# Precision_Adder.net
KiCad netlist of a schematic drawn in EAGLE
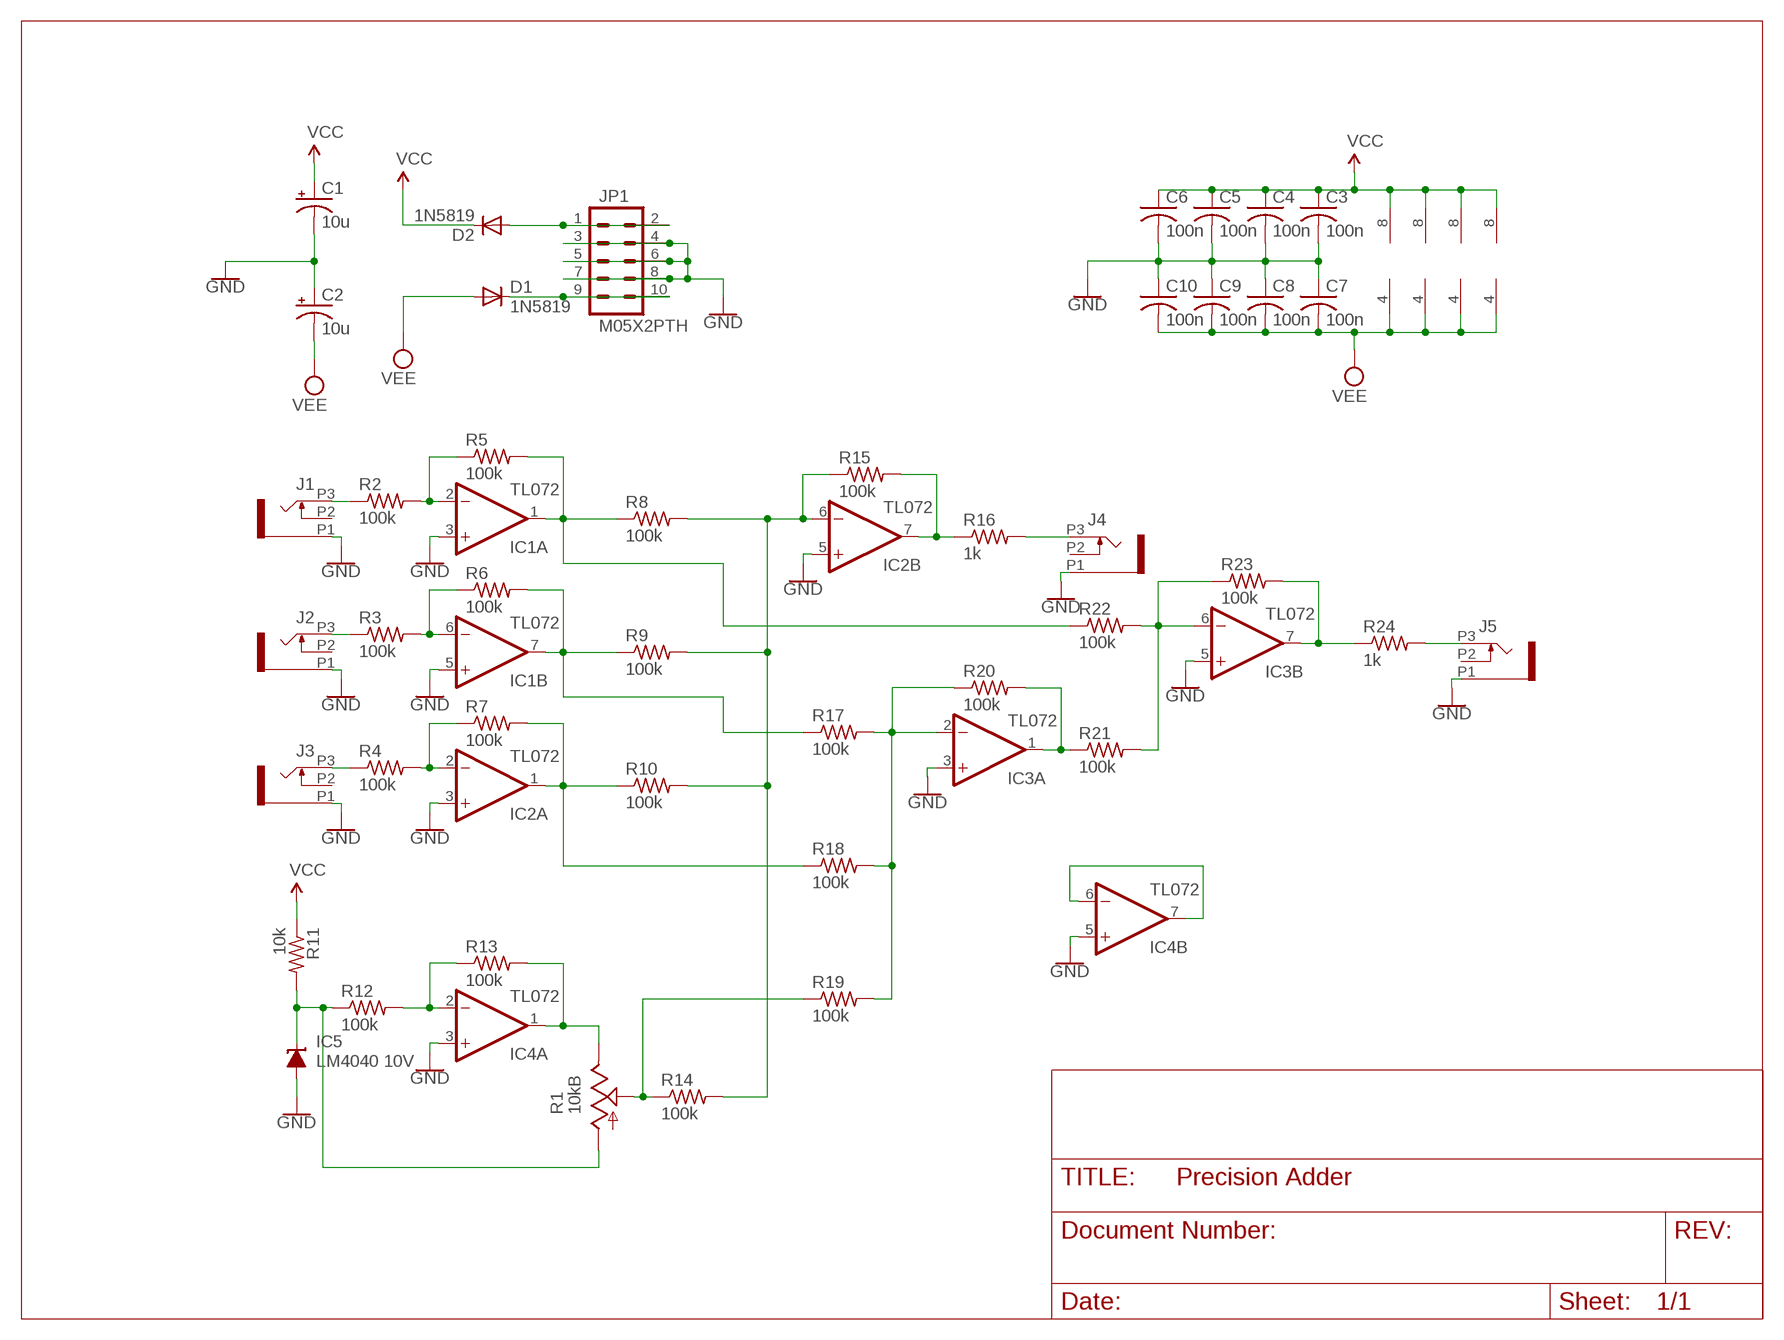
[diagram p0: schematic, sheet 1]

(export (version "E")
  (design (tool "Eeschema 10.0.6"))
  (components
    (comp (ref "C1")
      (value "10u")
      (footprint "eagle-import:RCL_PANASONIC_B")
      (libsource (lib "eagle-import") (part "RCL_CPOL-USB"))
    )
    (comp (ref "C2")
      (value "10u")
      (footprint "eagle-import:RCL_PANASONIC_B")
      (libsource (lib "eagle-import") (part "RCL_CPOL-USB"))
    )
    (comp (ref "C3")
      (value "100n")
      (footprint "eagle-import:RCL_C0603")
      (libsource (lib "eagle-import") (part "RCL_C-USC0603"))
    )
    (comp (ref "C4")
      (value "100n")
      (footprint "eagle-import:RCL_C0603")
      (libsource (lib "eagle-import") (part "RCL_C-USC0603"))
    )
    (comp (ref "C5")
      (value "100n")
      (footprint "eagle-import:RCL_C0603")
      (libsource (lib "eagle-import") (part "RCL_C-USC0603"))
    )
    (comp (ref "C6")
      (value "100n")
      (footprint "eagle-import:RCL_C0603")
      (libsource (lib "eagle-import") (part "RCL_C-USC0603"))
    )
    (comp (ref "C7")
      (value "100n")
      (footprint "eagle-import:RCL_C0603")
      (libsource (lib "eagle-import") (part "RCL_C-USC0603"))
    )
    (comp (ref "C8")
      (value "100n")
      (footprint "eagle-import:RCL_C0603")
      (libsource (lib "eagle-import") (part "RCL_C-USC0603"))
    )
    (comp (ref "C9")
      (value "100n")
      (footprint "eagle-import:RCL_C0603")
      (libsource (lib "eagle-import") (part "RCL_C-USC0603"))
    )
    (comp (ref "C10")
      (value "100n")
      (footprint "eagle-import:RCL_C0603")
      (libsource (lib "eagle-import") (part "RCL_C-USC0603"))
    )
    (comp (ref "D1")
      (value "1N5819")
      (footprint "eagle-import:DIODE_SOD123")
      (libsource (lib "eagle-import") (part "DIODE_DIODE-SOD123"))
    )
    (comp (ref "D2")
      (value "1N5819")
      (footprint "eagle-import:DIODE_SOD123")
      (libsource (lib "eagle-import") (part "DIODE_DIODE-SOD123"))
    )
    (comp (ref "IC1")
      (value "TL072")
      (footprint "eagle-import:GM-ICS_SO08")
      (libsource (lib "eagle-import") (part "GM-ICS_TL072D"))
    )
    (comp (ref "IC2")
      (value "TL072")
      (footprint "eagle-import:GM-ICS_SO08")
      (libsource (lib "eagle-import") (part "GM-ICS_TL072D"))
    )
    (comp (ref "IC3")
      (value "TL072")
      (footprint "eagle-import:GM-ICS_SO08")
      (libsource (lib "eagle-import") (part "GM-ICS_TL072D"))
    )
    (comp (ref "IC4")
      (value "TL072")
      (footprint "eagle-import:GM-ICS_SO08")
      (libsource (lib "eagle-import") (part "GM-ICS_TL072D"))
    )
    (comp (ref "IC5")
      (value "LM4040 10V")
      (footprint "eagle-import:TEXAS_DBZ_R-PDSO-G3")
      (libsource (lib "eagle-import") (part "TEXAS_LM4041DBZA12"))
    )
    (comp (ref "J1")
      (value "OG-PJ301_PJ301_THONKICONN6")
      (footprint "eagle-import:OG-PJ301_WQP_PJ_301M6")
      (libsource (lib "eagle-import") (part "OG-PJ301_PJ301_THONKICONN6"))
    )
    (comp (ref "J2")
      (value "OG-PJ301_PJ301_THONKICONN6")
      (footprint "eagle-import:OG-PJ301_WQP_PJ_301M6")
      (libsource (lib "eagle-import") (part "OG-PJ301_PJ301_THONKICONN6"))
    )
    (comp (ref "J3")
      (value "OG-PJ301_PJ301_THONKICONN6")
      (footprint "eagle-import:OG-PJ301_WQP_PJ_301M6")
      (libsource (lib "eagle-import") (part "OG-PJ301_PJ301_THONKICONN6"))
    )
    (comp (ref "J4")
      (value "OG-PJ301_PJ301_THONKICONN6")
      (footprint "eagle-import:OG-PJ301_WQP_PJ_301M6")
      (libsource (lib "eagle-import") (part "OG-PJ301_PJ301_THONKICONN6"))
    )
    (comp (ref "J5")
      (value "OG-PJ301_PJ301_THONKICONN6")
      (footprint "eagle-import:OG-PJ301_WQP_PJ_301M6")
      (libsource (lib "eagle-import") (part "OG-PJ301_PJ301_THONKICONN6"))
    )
    (comp (ref "JP1")
      (value "M05X2PTH")
      (footprint "eagle-import:OG-HEADER_AVR_ICSP")
      (libsource (lib "eagle-import") (part "OG-HEADER_M05X2PTH"))
    )
    (comp (ref "R1")
      (value "10kB")
      (footprint "eagle-import:POT-ALPS_ALPS_POT_VERTICAL_PS")
      (libsource (lib "eagle-import") (part "POT-ALPS_POT_USVERTICAL_PS"))
    )
    (comp (ref "R2")
      (value "100k")
      (footprint "eagle-import:RESISTOR_R0603")
      (libsource (lib "eagle-import") (part "RESISTOR_R-US_R0603"))
    )
    (comp (ref "R3")
      (value "100k")
      (footprint "eagle-import:RESISTOR_R0603")
      (libsource (lib "eagle-import") (part "RESISTOR_R-US_R0603"))
    )
    (comp (ref "R4")
      (value "100k")
      (footprint "eagle-import:RESISTOR_R0603")
      (libsource (lib "eagle-import") (part "RESISTOR_R-US_R0603"))
    )
    (comp (ref "R5")
      (value "100k")
      (footprint "eagle-import:RESISTOR_R0603")
      (libsource (lib "eagle-import") (part "RESISTOR_R-US_R0603"))
    )
    (comp (ref "R6")
      (value "100k")
      (footprint "eagle-import:RESISTOR_R0603")
      (libsource (lib "eagle-import") (part "RESISTOR_R-US_R0603"))
    )
    (comp (ref "R7")
      (value "100k")
      (footprint "eagle-import:RESISTOR_R0603")
      (libsource (lib "eagle-import") (part "RESISTOR_R-US_R0603"))
    )
    (comp (ref "R8")
      (value "100k")
      (footprint "eagle-import:RESISTOR_R0603")
      (libsource (lib "eagle-import") (part "RESISTOR_R-US_R0603"))
    )
    (comp (ref "R9")
      (value "100k")
      (footprint "eagle-import:RESISTOR_R0603")
      (libsource (lib "eagle-import") (part "RESISTOR_R-US_R0603"))
    )
    (comp (ref "R10")
      (value "100k")
      (footprint "eagle-import:RESISTOR_R0603")
      (libsource (lib "eagle-import") (part "RESISTOR_R-US_R0603"))
    )
    (comp (ref "R11")
      (value "10k")
      (footprint "eagle-import:RESISTOR_R0603")
      (libsource (lib "eagle-import") (part "RESISTOR_R-US_R0603"))
    )
    (comp (ref "R12")
      (value "100k")
      (footprint "eagle-import:RESISTOR_R0603")
      (libsource (lib "eagle-import") (part "RESISTOR_R-US_R0603"))
    )
    (comp (ref "R13")
      (value "100k")
      (footprint "eagle-import:RESISTOR_R0603")
      (libsource (lib "eagle-import") (part "RESISTOR_R-US_R0603"))
    )
    (comp (ref "R14")
      (value "100k")
      (footprint "eagle-import:RESISTOR_R0603")
      (libsource (lib "eagle-import") (part "RESISTOR_R-US_R0603"))
    )
    (comp (ref "R15")
      (value "100k")
      (footprint "eagle-import:RESISTOR_R0603")
      (libsource (lib "eagle-import") (part "RESISTOR_R-US_R0603"))
    )
    (comp (ref "R16")
      (value "1k")
      (footprint "eagle-import:RESISTOR_R0603")
      (libsource (lib "eagle-import") (part "RESISTOR_R-US_R0603"))
    )
    (comp (ref "R17")
      (value "100k")
      (footprint "eagle-import:RESISTOR_R0603")
      (libsource (lib "eagle-import") (part "RESISTOR_R-US_R0603"))
    )
    (comp (ref "R18")
      (value "100k")
      (footprint "eagle-import:RESISTOR_R0603")
      (libsource (lib "eagle-import") (part "RESISTOR_R-US_R0603"))
    )
    (comp (ref "R19")
      (value "100k")
      (footprint "eagle-import:RESISTOR_R0603")
      (libsource (lib "eagle-import") (part "RESISTOR_R-US_R0603"))
    )
    (comp (ref "R20")
      (value "100k")
      (footprint "eagle-import:RESISTOR_R0603")
      (libsource (lib "eagle-import") (part "RESISTOR_R-US_R0603"))
    )
    (comp (ref "R21")
      (value "100k")
      (footprint "eagle-import:RESISTOR_R0603")
      (libsource (lib "eagle-import") (part "RESISTOR_R-US_R0603"))
    )
    (comp (ref "R22")
      (value "100k")
      (footprint "eagle-import:RESISTOR_R0603")
      (libsource (lib "eagle-import") (part "RESISTOR_R-US_R0603"))
    )
    (comp (ref "R23")
      (value "100k")
      (footprint "eagle-import:RESISTOR_R0603")
      (libsource (lib "eagle-import") (part "RESISTOR_R-US_R0603"))
    )
    (comp (ref "R24")
      (value "1k")
      (footprint "eagle-import:RESISTOR_R0603")
      (libsource (lib "eagle-import") (part "RESISTOR_R-US_R0603"))
    )
  )
  (nets
    (net (code "1") (name "GND") (class "Default")
      (node (ref "C1") (pin "-") (pinfunction "-_-") (pintype "passive"))
      (node (ref "C10") (pin "1") (pinfunction "1_1") (pintype "passive"))
      (node (ref "C2") (pin "+") (pinfunction "+_+") (pintype "passive"))
      (node (ref "C3") (pin "2") (pinfunction "2_2") (pintype "passive"))
      (node (ref "C4") (pin "2") (pinfunction "2_2") (pintype "passive"))
      (node (ref "C5") (pin "2") (pinfunction "2_2") (pintype "passive"))
      (node (ref "C6") (pin "2") (pinfunction "2_2") (pintype "passive"))
      (node (ref "C7") (pin "1") (pinfunction "1_1") (pintype "passive"))
      (node (ref "C8") (pin "1") (pinfunction "1_1") (pintype "passive"))
      (node (ref "C9") (pin "1") (pinfunction "1_1") (pintype "passive"))
      (node (ref "IC1") (pin "3") (pinfunction "+IN_3") (pintype "input"))
      (node (ref "IC1") (pin "5") (pinfunction "+IN_5") (pintype "input"))
      (node (ref "IC2") (pin "3") (pinfunction "+IN_3") (pintype "input"))
      (node (ref "IC2") (pin "5") (pinfunction "+IN_5") (pintype "input"))
      (node (ref "IC3") (pin "3") (pinfunction "+IN_3") (pintype "input"))
      (node (ref "IC3") (pin "5") (pinfunction "+IN_5") (pintype "input"))
      (node (ref "IC4") (pin "3") (pinfunction "+IN_3") (pintype "input"))
      (node (ref "IC4") (pin "5") (pinfunction "+IN_5") (pintype "input"))
      (node (ref "IC5") (pin "2") (pinfunction "A_2") (pintype "passive"))
      (node (ref "J1") (pin "P1") (pinfunction "1_P1") (pintype "passive"))
      (node (ref "J2") (pin "P1") (pinfunction "1_P1") (pintype "passive"))
      (node (ref "J3") (pin "P1") (pinfunction "1_P1") (pintype "passive"))
      (node (ref "J4") (pin "P1") (pinfunction "1_P1") (pintype "passive"))
      (node (ref "J5") (pin "P1") (pinfunction "1_P1") (pintype "passive"))
      (node (ref "JP1") (pin "3") (pinfunction "3_3") (pintype "passive"))
      (node (ref "JP1") (pin "4") (pinfunction "4_4") (pintype "passive"))
      (node (ref "JP1") (pin "5") (pinfunction "5_5") (pintype "passive"))
      (node (ref "JP1") (pin "6") (pinfunction "6_6") (pintype "passive"))
      (node (ref "JP1") (pin "7") (pinfunction "7_7") (pintype "passive"))
      (node (ref "JP1") (pin "8") (pinfunction "8_8") (pintype "passive"))
    )
    (net (code "2") (name "Net-(D1-PadC)") (class "Default")
      (node (ref "D1") (pin "C") (pinfunction "C_C") (pintype "passive"))
      (node (ref "JP1") (pin "10") (pinfunction "10_10") (pintype "passive"))
      (node (ref "JP1") (pin "9") (pinfunction "9_9") (pintype "passive"))
    )
    (net (code "3") (name "Net-(D2-PadA)") (class "Default")
      (node (ref "D2") (pin "A") (pinfunction "A_A") (pintype "passive"))
      (node (ref "JP1") (pin "1") (pinfunction "1_1") (pintype "passive"))
      (node (ref "JP1") (pin "2") (pinfunction "2_2") (pintype "passive"))
    )
    (net (code "4") (name "Net-(IC1A--IN)") (class "Default")
      (node (ref "IC1") (pin "2") (pinfunction "-IN_2") (pintype "input"))
      (node (ref "R2") (pin "2") (pinfunction "2_2") (pintype "passive"))
      (node (ref "R5") (pin "1") (pinfunction "1_1") (pintype "passive"))
    )
    (net (code "5") (name "Net-(IC1A-OUT)") (class "Default")
      (node (ref "IC1") (pin "1") (pinfunction "OUT_1") (pintype "output"))
      (node (ref "R22") (pin "1") (pinfunction "1_1") (pintype "passive"))
      (node (ref "R5") (pin "2") (pinfunction "2_2") (pintype "passive"))
      (node (ref "R8") (pin "1") (pinfunction "1_1") (pintype "passive"))
    )
    (net (code "6") (name "Net-(IC1B--IN)") (class "Default")
      (node (ref "IC1") (pin "6") (pinfunction "-IN_6") (pintype "input"))
      (node (ref "R3") (pin "2") (pinfunction "2_2") (pintype "passive"))
      (node (ref "R6") (pin "1") (pinfunction "1_1") (pintype "passive"))
    )
    (net (code "7") (name "Net-(IC1B-OUT)") (class "Default")
      (node (ref "IC1") (pin "7") (pinfunction "OUT_7") (pintype "output"))
      (node (ref "R17") (pin "1") (pinfunction "1_1") (pintype "passive"))
      (node (ref "R6") (pin "2") (pinfunction "2_2") (pintype "passive"))
      (node (ref "R9") (pin "1") (pinfunction "1_1") (pintype "passive"))
    )
    (net (code "8") (name "Net-(IC2A--IN)") (class "Default")
      (node (ref "IC2") (pin "2") (pinfunction "-IN_2") (pintype "input"))
      (node (ref "R4") (pin "2") (pinfunction "2_2") (pintype "passive"))
      (node (ref "R7") (pin "1") (pinfunction "1_1") (pintype "passive"))
    )
    (net (code "9") (name "Net-(IC2A-OUT)") (class "Default")
      (node (ref "IC2") (pin "1") (pinfunction "OUT_1") (pintype "output"))
      (node (ref "R10") (pin "1") (pinfunction "1_1") (pintype "passive"))
      (node (ref "R18") (pin "1") (pinfunction "1_1") (pintype "passive"))
      (node (ref "R7") (pin "2") (pinfunction "2_2") (pintype "passive"))
    )
    (net (code "10") (name "Net-(IC2B--IN)") (class "Default")
      (node (ref "IC2") (pin "6") (pinfunction "-IN_6") (pintype "input"))
      (node (ref "R10") (pin "2") (pinfunction "2_2") (pintype "passive"))
      (node (ref "R14") (pin "2") (pinfunction "2_2") (pintype "passive"))
      (node (ref "R15") (pin "1") (pinfunction "1_1") (pintype "passive"))
      (node (ref "R8") (pin "2") (pinfunction "2_2") (pintype "passive"))
      (node (ref "R9") (pin "2") (pinfunction "2_2") (pintype "passive"))
    )
    (net (code "11") (name "Net-(IC2B-OUT)") (class "Default")
      (node (ref "IC2") (pin "7") (pinfunction "OUT_7") (pintype "output"))
      (node (ref "R15") (pin "2") (pinfunction "2_2") (pintype "passive"))
      (node (ref "R16") (pin "1") (pinfunction "1_1") (pintype "passive"))
    )
    (net (code "12") (name "Net-(IC3A--IN)") (class "Default")
      (node (ref "IC3") (pin "2") (pinfunction "-IN_2") (pintype "input"))
      (node (ref "R17") (pin "2") (pinfunction "2_2") (pintype "passive"))
      (node (ref "R18") (pin "2") (pinfunction "2_2") (pintype "passive"))
      (node (ref "R19") (pin "2") (pinfunction "2_2") (pintype "passive"))
      (node (ref "R20") (pin "1") (pinfunction "1_1") (pintype "passive"))
    )
    (net (code "13") (name "Net-(IC3A-OUT)") (class "Default")
      (node (ref "IC3") (pin "1") (pinfunction "OUT_1") (pintype "output"))
      (node (ref "R20") (pin "2") (pinfunction "2_2") (pintype "passive"))
      (node (ref "R21") (pin "1") (pinfunction "1_1") (pintype "passive"))
    )
    (net (code "14") (name "Net-(IC3B--IN)") (class "Default")
      (node (ref "IC3") (pin "6") (pinfunction "-IN_6") (pintype "input"))
      (node (ref "R21") (pin "2") (pinfunction "2_2") (pintype "passive"))
      (node (ref "R22") (pin "2") (pinfunction "2_2") (pintype "passive"))
      (node (ref "R23") (pin "1") (pinfunction "1_1") (pintype "passive"))
    )
    (net (code "15") (name "Net-(IC3B-OUT)") (class "Default")
      (node (ref "IC3") (pin "7") (pinfunction "OUT_7") (pintype "output"))
      (node (ref "R23") (pin "2") (pinfunction "2_2") (pintype "passive"))
      (node (ref "R24") (pin "1") (pinfunction "1_1") (pintype "passive"))
    )
    (net (code "16") (name "Net-(IC4A--IN)") (class "Default")
      (node (ref "IC4") (pin "2") (pinfunction "-IN_2") (pintype "input"))
      (node (ref "R12") (pin "2") (pinfunction "2_2") (pintype "passive"))
      (node (ref "R13") (pin "1") (pinfunction "1_1") (pintype "passive"))
    )
    (net (code "17") (name "Net-(IC4A-OUT)") (class "Default")
      (node (ref "IC4") (pin "1") (pinfunction "OUT_1") (pintype "output"))
      (node (ref "R1") (pin "P$1") (pinfunction "E_P$1") (pintype "passive"))
      (node (ref "R13") (pin "2") (pinfunction "2_2") (pintype "passive"))
    )
    (net (code "18") (name "Net-(IC4B--IN)") (class "Default")
      (node (ref "IC4") (pin "6") (pinfunction "-IN_6") (pintype "input"))
      (node (ref "IC4") (pin "7") (pinfunction "OUT_7") (pintype "output"))
    )
    (net (code "19") (name "Net-(IC5-C)") (class "Default")
      (node (ref "IC5") (pin "1") (pinfunction "C_1") (pintype "passive"))
      (node (ref "R1") (pin "P$3") (pinfunction "A_P$3") (pintype "passive"))
      (node (ref "R11") (pin "2") (pinfunction "2_2") (pintype "passive"))
      (node (ref "R12") (pin "1") (pinfunction "1_1") (pintype "passive"))
    )
    (net (code "20") (name "Net-(J1-3)") (class "Default")
      (node (ref "J1") (pin "P3") (pinfunction "3_P3") (pintype "passive"))
      (node (ref "R2") (pin "1") (pinfunction "1_1") (pintype "passive"))
    )
    (net (code "21") (name "Net-(J2-3)") (class "Default")
      (node (ref "J2") (pin "P3") (pinfunction "3_P3") (pintype "passive"))
      (node (ref "R3") (pin "1") (pinfunction "1_1") (pintype "passive"))
    )
    (net (code "22") (name "Net-(J3-3)") (class "Default")
      (node (ref "J3") (pin "P3") (pinfunction "3_P3") (pintype "passive"))
      (node (ref "R4") (pin "1") (pinfunction "1_1") (pintype "passive"))
    )
    (net (code "23") (name "Net-(J4-3)") (class "Default")
      (node (ref "J4") (pin "P3") (pinfunction "3_P3") (pintype "passive"))
      (node (ref "R16") (pin "2") (pinfunction "2_2") (pintype "passive"))
    )
    (net (code "24") (name "Net-(J5-3)") (class "Default")
      (node (ref "J5") (pin "P3") (pinfunction "3_P3") (pintype "passive"))
      (node (ref "R24") (pin "2") (pinfunction "2_2") (pintype "passive"))
    )
    (net (code "25") (name "Net-(R1-S)") (class "Default")
      (node (ref "R1") (pin "P$2") (pinfunction "S_P$2") (pintype "passive"))
      (node (ref "R14") (pin "1") (pinfunction "1_1") (pintype "passive"))
      (node (ref "R19") (pin "1") (pinfunction "1_1") (pintype "passive"))
    )
    (net (code "26") (name "VCC") (class "Default")
      (node (ref "C1") (pin "+") (pinfunction "+_+") (pintype "passive"))
      (node (ref "C3") (pin "1") (pinfunction "1_1") (pintype "passive"))
      (node (ref "C4") (pin "1") (pinfunction "1_1") (pintype "passive"))
      (node (ref "C5") (pin "1") (pinfunction "1_1") (pintype "passive"))
      (node (ref "C6") (pin "1") (pinfunction "1_1") (pintype "passive"))
      (node (ref "D2") (pin "C") (pinfunction "C_C") (pintype "passive"))
      (node (ref "IC1") (pin "8") (pinfunction "V+_8") (pintype "power_in"))
      (node (ref "IC2") (pin "8") (pinfunction "V+_8") (pintype "power_in"))
      (node (ref "IC3") (pin "8") (pinfunction "V+_8") (pintype "power_in"))
      (node (ref "IC4") (pin "8") (pinfunction "V+_8") (pintype "power_in"))
      (node (ref "R11") (pin "1") (pinfunction "1_1") (pintype "passive"))
    )
    (net (code "27") (name "VEE") (class "Default")
      (node (ref "C10") (pin "2") (pinfunction "2_2") (pintype "passive"))
      (node (ref "C2") (pin "-") (pinfunction "-_-") (pintype "passive"))
      (node (ref "C7") (pin "2") (pinfunction "2_2") (pintype "passive"))
      (node (ref "C8") (pin "2") (pinfunction "2_2") (pintype "passive"))
      (node (ref "C9") (pin "2") (pinfunction "2_2") (pintype "passive"))
      (node (ref "D1") (pin "A") (pinfunction "A_A") (pintype "passive"))
      (node (ref "IC1") (pin "4") (pinfunction "V-_4") (pintype "power_in"))
      (node (ref "IC2") (pin "4") (pinfunction "V-_4") (pintype "power_in"))
      (node (ref "IC3") (pin "4") (pinfunction "V-_4") (pintype "power_in"))
      (node (ref "IC4") (pin "4") (pinfunction "V-_4") (pintype "power_in"))
    )
    (net (code "28") (name "unconnected-(J1-2-PadP2)") (class "Default")
      (node (ref "J1") (pin "P2") (pinfunction "2_P2") (pintype "passive"))
    )
    (net (code "29") (name "unconnected-(J2-2-PadP2)") (class "Default")
      (node (ref "J2") (pin "P2") (pinfunction "2_P2") (pintype "passive"))
    )
    (net (code "30") (name "unconnected-(J3-2-PadP2)") (class "Default")
      (node (ref "J3") (pin "P2") (pinfunction "2_P2") (pintype "passive"))
    )
    (net (code "31") (name "unconnected-(J4-2-PadP2)") (class "Default")
      (node (ref "J4") (pin "P2") (pinfunction "2_P2") (pintype "passive"))
    )
    (net (code "32") (name "unconnected-(J5-2-PadP2)") (class "Default")
      (node (ref "J5") (pin "P2") (pinfunction "2_P2") (pintype "passive"))
    )
  )
)
